# prod_plus_l-filters_v2.net
KiCad netlist of a schematic drawn in EAGLE
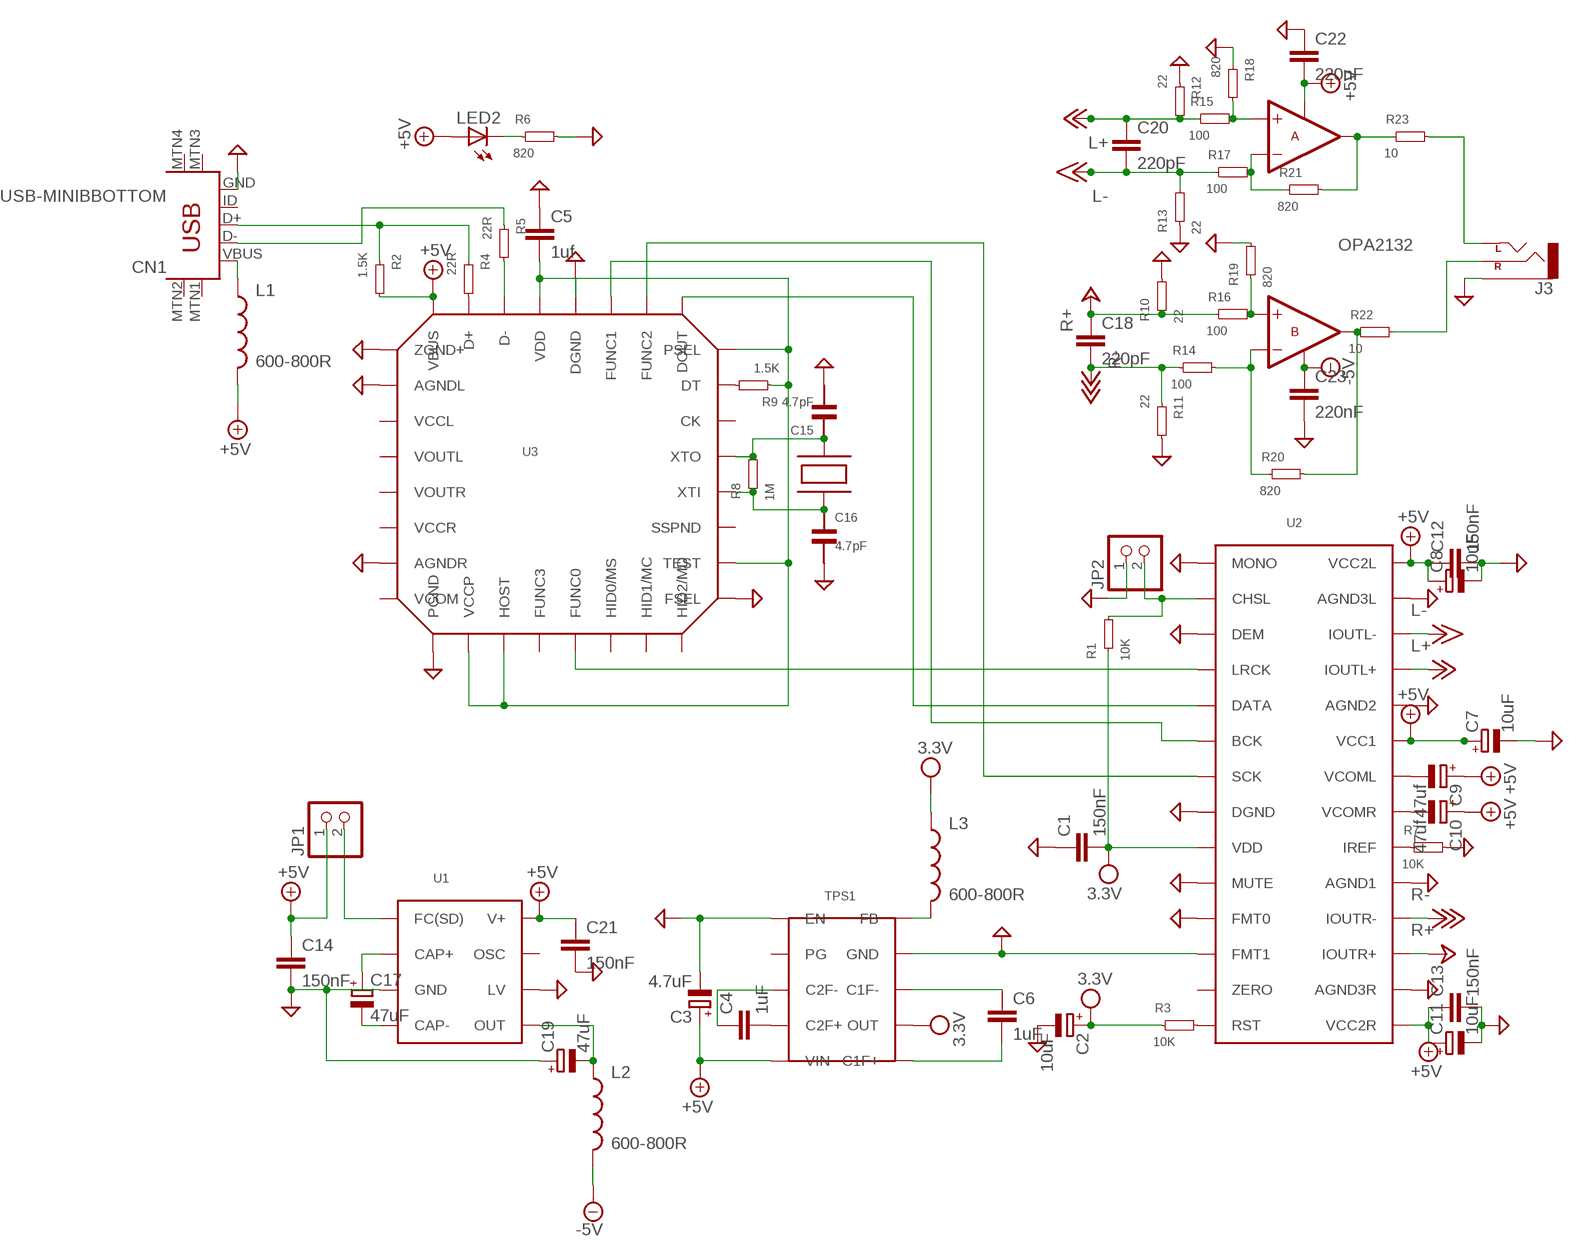
[diagram p0: schematic, sheet 1]

(export (version "E")
  (design (tool "Eeschema 10.0.6"))
  (components
    (comp (ref "C1")
      (value "150nF")
      (footprint "eagle-import:0805")
      (libsource (lib "eagle-import") (part "CAP0805"))
    )
    (comp (ref "C2")
      (value "10uF")
      (footprint "eagle-import:10UF_16V_PANA_M_CAP")
      (libsource (lib "eagle-import") (part "10UF/16V_PANA_M-CAP"))
    )
    (comp (ref "C3")
      (value "4.7uF")
      (footprint "eagle-import:10UF_16V_PANA_M_CAP")
      (libsource (lib "eagle-import") (part "4.7UF/50V_PANA_M-CAP"))
    )
    (comp (ref "C4")
      (value "1uF")
      (footprint "eagle-import:0805")
      (libsource (lib "eagle-import") (part "CAP0805"))
    )
    (comp (ref "C5")
      (value "1uf")
      (footprint "eagle-import:0805")
      (libsource (lib "eagle-import") (part "CAP0805"))
    )
    (comp (ref "C6")
      (value "1uF")
      (footprint "eagle-import:0805")
      (libsource (lib "eagle-import") (part "CAP0805"))
    )
    (comp (ref "C7")
      (value "10uF")
      (footprint "eagle-import:10UF_16V_PANA_M_CAP")
      (libsource (lib "eagle-import") (part "10UF/16V_PANA_M-CAP"))
    )
    (comp (ref "C8")
      (value "10uF")
      (footprint "eagle-import:10UF_16V_PANA_M_CAP")
      (libsource (lib "eagle-import") (part "10UF/16V_PANA_M-CAP"))
    )
    (comp (ref "C9")
      (value "47uf")
      (footprint "eagle-import:10UF_16V_PANA_M_CAP")
      (libsource (lib "eagle-import") (part "47UF/16V_PANA_M-CAP"))
    )
    (comp (ref "C10")
      (value "47uf")
      (footprint "eagle-import:10UF_16V_PANA_M_CAP")
      (libsource (lib "eagle-import") (part "47UF/16V_PANA_M-CAP"))
    )
    (comp (ref "C11")
      (value "10uF")
      (footprint "eagle-import:10UF_16V_PANA_M_CAP")
      (libsource (lib "eagle-import") (part "10UF/16V_PANA_M-CAP"))
    )
    (comp (ref "C12")
      (value "150nF")
      (footprint "eagle-import:0805")
      (libsource (lib "eagle-import") (part "CAP0805"))
    )
    (comp (ref "C13")
      (value "150nF")
      (footprint "eagle-import:0805")
      (libsource (lib "eagle-import") (part "CAP0805"))
    )
    (comp (ref "C14")
      (value "150nF")
      (footprint "eagle-import:0805")
      (libsource (lib "eagle-import") (part "CAP0805"))
    )
    (comp (ref "C15")
      (value "4.7pF")
      (footprint "eagle-import:4.7PF_CAP")
      (libsource (lib "eagle-import") (part "4.7PF_CAPMLCC"))
    )
    (comp (ref "C16")
      (value "4.7pF")
      (footprint "eagle-import:4.7PF_CAP")
      (libsource (lib "eagle-import") (part "4.7PF_CAPMLCC"))
    )
    (comp (ref "C17")
      (value "47uF")
      (footprint "eagle-import:10UF_16V_PANA_M_CAP")
      (libsource (lib "eagle-import") (part "47UF/16V_PANA_M-CAP"))
    )
    (comp (ref "C18")
      (value "220pF")
      (footprint "eagle-import:C050-045X075")
      (libsource (lib "eagle-import") (part "C-EU050-045X075"))
    )
    (comp (ref "C19")
      (value "47uF")
      (footprint "eagle-import:10UF_16V_PANA_M_CAP")
      (libsource (lib "eagle-import") (part "47UF/16V_PANA_M-CAP"))
    )
    (comp (ref "C20")
      (value "220pF")
      (footprint "eagle-import:C050-045X075")
      (libsource (lib "eagle-import") (part "C-EU050-045X075"))
    )
    (comp (ref "C21")
      (value "150nF")
      (footprint "eagle-import:0805")
      (libsource (lib "eagle-import") (part "CAP0805"))
    )
    (comp (ref "C22")
      (value "220nF")
      (footprint "eagle-import:0805")
      (libsource (lib "eagle-import") (part "22UF-6.3V-20%(0805)"))
    )
    (comp (ref "C23")
      (value "220nF")
      (footprint "eagle-import:0805")
      (libsource (lib "eagle-import") (part "22UF-6.3V-20%(0805)"))
    )
    (comp (ref "CN1")
      (value "USB-MINIBBOTTOM")
      (footprint "eagle-import:USB-MINIB")
      (libsource (lib "eagle-import") (part "USB-MINIBBOTTOM"))
    )
    (comp (ref "J3")
      (value "AUDIO-JACKPTH")
      (footprint "eagle-import:AUDIO-JACK")
      (libsource (lib "eagle-import") (part "AUDIO-JACKPTH"))
    )
    (comp (ref "JP1")
      (value "PINHD-1X2")
      (footprint "eagle-import:1X02")
      (libsource (lib "eagle-import") (part "PINHD-1X2"))
    )
    (comp (ref "JP2")
      (value "PINHD-1X2")
      (footprint "eagle-import:1X02")
      (libsource (lib "eagle-import") (part "PINHD-1X2"))
    )
    (comp (ref "L1")
      (value "600-800R")
      (footprint "eagle-import:0805")
      (libsource (lib "eagle-import") (part "INDUCTOR0805-IND"))
    )
    (comp (ref "L2")
      (value "600-800R")
      (footprint "eagle-import:0805")
      (libsource (lib "eagle-import") (part "INDUCTOR0805-IND"))
    )
    (comp (ref "L3")
      (value "600-800R")
      (footprint "eagle-import:0805")
      (libsource (lib "eagle-import") (part "INDUCTOR0805-IND"))
    )
    (comp (ref "LED2")
      (value "LED3MM")
      (footprint "eagle-import:LED3MM")
      (libsource (lib "eagle-import") (part "LED3MM"))
    )
    (comp (ref "OPA2132")
      (value "OPA2132DIP8")
      (footprint "eagle-import:DIP-8")
      (libsource (lib "eagle-import") (part "OPA2132DIP8"))
    )
    (comp (ref "R1")
      (value "10K")
      (footprint "eagle-import:1-8W_RES")
      (libsource (lib "eagle-import") (part "RESISTOR.125W"))
    )
    (comp (ref "R2")
      (value "1.5K")
      (footprint "eagle-import:1-8W_RES")
      (libsource (lib "eagle-import") (part "RESISTOR.125W"))
    )
    (comp (ref "R3")
      (value "10K")
      (footprint "eagle-import:1-8W_RES")
      (libsource (lib "eagle-import") (part "RESISTOR.125W"))
    )
    (comp (ref "R4")
      (value "22R")
      (footprint "eagle-import:1-8W_RES")
      (libsource (lib "eagle-import") (part "RESISTOR.125W"))
    )
    (comp (ref "R5")
      (value "22R")
      (footprint "eagle-import:1-8W_RES")
      (libsource (lib "eagle-import") (part "RESISTOR.125W"))
    )
    (comp (ref "R6")
      (value "820")
      (footprint "eagle-import:1-8W_RES")
      (libsource (lib "eagle-import") (part "RESISTOR.125W"))
    )
    (comp (ref "R7")
      (value "10K")
      (footprint "eagle-import:1-8W_RES")
      (libsource (lib "eagle-import") (part "RESISTOR.125W"))
    )
    (comp (ref "R8")
      (value "1M")
      (footprint "eagle-import:1-8W_RES")
      (libsource (lib "eagle-import") (part "RESISTOR.125W"))
    )
    (comp (ref "R9")
      (value "1.5K")
      (footprint "eagle-import:1-8W_RES")
      (libsource (lib "eagle-import") (part "RESISTOR.125W"))
    )
    (comp (ref "R10")
      (value "22")
      (footprint "eagle-import:1-8W_RES")
      (libsource (lib "eagle-import") (part "RESISTOR.125W"))
    )
    (comp (ref "R11")
      (value "22")
      (footprint "eagle-import:1-8W_RES")
      (libsource (lib "eagle-import") (part "RESISTOR.125W"))
    )
    (comp (ref "R12")
      (value "22")
      (footprint "eagle-import:1-8W_RES")
      (libsource (lib "eagle-import") (part "RESISTOR.125W"))
    )
    (comp (ref "R13")
      (value "22")
      (footprint "eagle-import:1-8W_RES")
      (libsource (lib "eagle-import") (part "RESISTOR.125W"))
    )
    (comp (ref "R14")
      (value "100")
      (footprint "eagle-import:1-8W_RES")
      (libsource (lib "eagle-import") (part "RESISTOR.125W"))
    )
    (comp (ref "R15")
      (value "100")
      (footprint "eagle-import:1-8W_RES")
      (libsource (lib "eagle-import") (part "RESISTOR.125W"))
    )
    (comp (ref "R16")
      (value "100")
      (footprint "eagle-import:1-8W_RES")
      (libsource (lib "eagle-import") (part "RESISTOR.125W"))
    )
    (comp (ref "R17")
      (value "100")
      (footprint "eagle-import:1-8W_RES")
      (libsource (lib "eagle-import") (part "RESISTOR.125W"))
    )
    (comp (ref "R18")
      (value "820")
      (footprint "eagle-import:1-8W_RES")
      (libsource (lib "eagle-import") (part "RESISTOR.125W"))
    )
    (comp (ref "R19")
      (value "820")
      (footprint "eagle-import:1-8W_RES")
      (libsource (lib "eagle-import") (part "RESISTOR.125W"))
    )
    (comp (ref "R20")
      (value "820")
      (footprint "eagle-import:1-8W_RES")
      (libsource (lib "eagle-import") (part "RESISTOR.125W"))
    )
    (comp (ref "R21")
      (value "820")
      (footprint "eagle-import:1-8W_RES")
      (libsource (lib "eagle-import") (part "RESISTOR.125W"))
    )
    (comp (ref "R22")
      (value "10")
      (footprint "eagle-import:1-8W_RES")
      (libsource (lib "eagle-import") (part "RESISTOR.125W"))
    )
    (comp (ref "R23")
      (value "10")
      (footprint "eagle-import:1-8W_RES")
      (libsource (lib "eagle-import") (part "RESISTOR.125W"))
    )
    (comp (ref "TPS1")
      (value "TPS60501DGS-10-BOTTOM")
      (footprint "eagle-import:DGS-10-BOTTOM_LYR")
      (libsource (lib "eagle-import") (part "TPS60501DGS-10-BOTTOM"))
    )
    (comp (ref "U1")
      (value "LM2662SO8-BOTTOM")
      (footprint "eagle-import:SOIC-8_BOTTOM-LYR")
      (libsource (lib "eagle-import") (part "LM2662SO8-BOTTOM"))
    )
    (comp (ref "U2")
      (value "PCM1794ADB_R-PDSO-G28-BOTTOM")
      (footprint "eagle-import:DB_R-PDSO-G28-BOTTOM_LYR")
      (libsource (lib "eagle-import") (part "PCM1794ADB_R-PDSO-G28-BOTTOM"))
    )
    (comp (ref "U3")
      (value "PCM2707QFP-32-BOTTOM")
      (footprint "eagle-import:PJT_(QFP-32)-BOTTOM_LYR")
      (libsource (lib "eagle-import") (part "PCM2707QFP-32-BOTTOM"))
    )
    (comp (ref "X1")
      (value "12MHZ")
      (footprint "eagle-import:CRYSTAL")
      (libsource (lib "eagle-import") (part "CRYSTAL"))
    )
  )
  (nets
    (net (code "1") (name "+5V") (class "Default")
      (node (ref "C10") (pin "+") (pinfunction "+_+") (pintype "passive"))
      (node (ref "C11") (pin "+") (pinfunction "+_+") (pintype "passive"))
      (node (ref "C12") (pin "1") (pinfunction "1_1") (pintype "passive"))
      (node (ref "C13") (pin "1") (pinfunction "1_1") (pintype "passive"))
      (node (ref "C14") (pin "1") (pinfunction "1_1") (pintype "passive"))
      (node (ref "C21") (pin "1") (pinfunction "1_1") (pintype "passive"))
      (node (ref "C22") (pin "2") (pinfunction "2_2") (pintype "passive"))
      (node (ref "C3") (pin "+") (pinfunction "+_+") (pintype "passive"))
      (node (ref "C7") (pin "+") (pinfunction "+_+") (pintype "passive"))
      (node (ref "C8") (pin "+") (pinfunction "+_+") (pintype "passive"))
      (node (ref "C9") (pin "+") (pinfunction "+_+") (pintype "passive"))
      (node (ref "JP1") (pin "1") (pinfunction "1_1") (pintype "passive"))
      (node (ref "L1") (pin "2") (pinfunction "2_2") (pintype "passive"))
      (node (ref "LED2") (pin "A") (pinfunction "A_A") (pintype "passive"))
      (node (ref "OPA2132") (pin "8") (pinfunction "8(+)_8") (pintype "bidirectional"))
      (node (ref "R2") (pin "P$2") (pinfunction "2_P$2") (pintype "bidirectional"))
      (node (ref "TPS1") (pin "5") (pinfunction "VIN_5") (pintype "bidirectional"))
      (node (ref "U1") (pin "8") (pinfunction "V+_8") (pintype "bidirectional"))
      (node (ref "U2") (pin "15") (pinfunction "VCC2R_15") (pintype "bidirectional"))
      (node (ref "U2") (pin "23") (pinfunction "VCC1_23") (pintype "bidirectional"))
      (node (ref "U2") (pin "28") (pinfunction "VCC2L_28") (pintype "bidirectional"))
      (node (ref "U3") (pin "24") (pinfunction "VBUS_24") (pintype "bidirectional"))
    )
    (net (code "2") (name "-5V") (class "Default")
      (node (ref "C23") (pin "1") (pinfunction "1_1") (pintype "passive"))
      (node (ref "L2") (pin "2") (pinfunction "2_2") (pintype "passive"))
      (node (ref "OPA2132") (pin "4") (pinfunction "4(-)_4") (pintype "bidirectional"))
    )
    (net (code "3") (name "3.3V") (class "Default")
      (node (ref "C1") (pin "2") (pinfunction "2_2") (pintype "passive"))
      (node (ref "C2") (pin "+") (pinfunction "+_+") (pintype "passive"))
      (node (ref "L3") (pin "1") (pinfunction "1_1") (pintype "passive"))
      (node (ref "R1") (pin "P$1") (pinfunction "1_P$1") (pintype "bidirectional"))
      (node (ref "R3") (pin "P$1") (pinfunction "1_P$1") (pintype "bidirectional"))
      (node (ref "TPS1") (pin "7") (pinfunction "OUT_7") (pintype "bidirectional"))
      (node (ref "U2") (pin "9") (pinfunction "VDD_9") (pintype "bidirectional"))
    )
    (net (code "4") (name "GND") (class "Default")
      (node (ref "C1") (pin "1") (pinfunction "1_1") (pintype "passive"))
      (node (ref "C11") (pin "-") (pinfunction "-_-") (pintype "passive"))
      (node (ref "C12") (pin "2") (pinfunction "2_2") (pintype "passive"))
      (node (ref "C13") (pin "2") (pinfunction "2_2") (pintype "passive"))
      (node (ref "C14") (pin "2") (pinfunction "2_2") (pintype "passive"))
      (node (ref "C15") (pin "2") (pinfunction "2_2") (pintype "bidirectional"))
      (node (ref "C16") (pin "2") (pinfunction "2_2") (pintype "bidirectional"))
      (node (ref "C19") (pin "+") (pinfunction "+_+") (pintype "passive"))
      (node (ref "C2") (pin "-") (pinfunction "-_-") (pintype "passive"))
      (node (ref "C21") (pin "2") (pinfunction "2_2") (pintype "passive"))
      (node (ref "C22") (pin "1") (pinfunction "1_1") (pintype "passive"))
      (node (ref "C23") (pin "2") (pinfunction "2_2") (pintype "passive"))
      (node (ref "C3") (pin "-") (pinfunction "-_-") (pintype "passive"))
      (node (ref "C5") (pin "1") (pinfunction "1_1") (pintype "passive"))
      (node (ref "C7") (pin "-") (pinfunction "-_-") (pintype "passive"))
      (node (ref "C8") (pin "-") (pinfunction "-_-") (pintype "passive"))
      (node (ref "CN1") (pin "GND") (pinfunction "GND_GND") (pintype "bidirectional"))
      (node (ref "J3") (pin "SLEEVE") (pinfunction "SLEEVE_SLEEVE") (pintype "bidirectional"))
      (node (ref "JP2") (pin "1") (pinfunction "1_1") (pintype "passive"))
      (node (ref "R10") (pin "P$2") (pinfunction "2_P$2") (pintype "bidirectional"))
      (node (ref "R11") (pin "P$2") (pinfunction "2_P$2") (pintype "bidirectional"))
      (node (ref "R12") (pin "P$1") (pinfunction "1_P$1") (pintype "bidirectional"))
      (node (ref "R13") (pin "P$1") (pinfunction "1_P$1") (pintype "bidirectional"))
      (node (ref "R18") (pin "P$1") (pinfunction "1_P$1") (pintype "bidirectional"))
      (node (ref "R19") (pin "P$2") (pinfunction "2_P$2") (pintype "bidirectional"))
      (node (ref "R6") (pin "P$2") (pinfunction "2_P$2") (pintype "bidirectional"))
      (node (ref "R7") (pin "P$2") (pinfunction "2_P$2") (pintype "bidirectional"))
      (node (ref "TPS1") (pin "1") (pinfunction "EN_1") (pintype "bidirectional"))
      (node (ref "TPS1") (pin "9") (pinfunction "GND_9") (pintype "bidirectional"))
      (node (ref "U1") (pin "3") (pinfunction "GND_3") (pintype "bidirectional"))
      (node (ref "U1") (pin "6") (pinfunction "LV_6") (pintype "bidirectional"))
      (node (ref "U2") (pin "1") (pinfunction "MONO_1") (pintype "bidirectional"))
      (node (ref "U2") (pin "10") (pinfunction "MUTE_10") (pintype "bidirectional"))
      (node (ref "U2") (pin "11") (pinfunction "FMT0_11") (pintype "bidirectional"))
      (node (ref "U2") (pin "12") (pinfunction "FMT1_12") (pintype "bidirectional"))
      (node (ref "U2") (pin "16") (pinfunction "AGND3R_16") (pintype "bidirectional"))
      (node (ref "U2") (pin "19") (pinfunction "AGND1_19") (pintype "bidirectional"))
      (node (ref "U2") (pin "24") (pinfunction "AGND2_24") (pintype "bidirectional"))
      (node (ref "U2") (pin "27") (pinfunction "AGND3L_27") (pintype "bidirectional"))
      (node (ref "U2") (pin "3") (pinfunction "DEM_3") (pintype "bidirectional"))
      (node (ref "U2") (pin "8") (pinfunction "DGND_8") (pintype "bidirectional"))
      (node (ref "U3") (pin "1") (pinfunction "PGND_1") (pintype "bidirectional"))
      (node (ref "U3") (pin "20") (pinfunction "DGND_20") (pintype "bidirectional"))
      (node (ref "U3") (pin "25") (pinfunction "ZGND+_25") (pintype "bidirectional"))
      (node (ref "U3") (pin "26") (pinfunction "AGNDL_26") (pintype "bidirectional"))
      (node (ref "U3") (pin "31") (pinfunction "AGNDR_31") (pintype "bidirectional"))
      (node (ref "U3") (pin "9") (pinfunction "FSEL_9") (pintype "bidirectional"))
    )
    (net (code "5") (name "L+") (class "Default")
      (node (ref "C20") (pin "1") (pinfunction "1_1") (pintype "passive"))
      (node (ref "R12") (pin "P$2") (pinfunction "2_P$2") (pintype "bidirectional"))
      (node (ref "R15") (pin "P$1") (pinfunction "1_P$1") (pintype "bidirectional"))
      (node (ref "U2") (pin "25") (pinfunction "IOUTL+_25") (pintype "bidirectional"))
    )
    (net (code "6") (name "L-") (class "Default")
      (node (ref "C20") (pin "2") (pinfunction "2_2") (pintype "passive"))
      (node (ref "R13") (pin "P$2") (pinfunction "2_P$2") (pintype "bidirectional"))
      (node (ref "R17") (pin "P$1") (pinfunction "1_P$1") (pintype "bidirectional"))
      (node (ref "U2") (pin "26") (pinfunction "IOUTL-_26") (pintype "bidirectional"))
    )
    (net (code "7") (name "Net-(CN1-PadVBUS)") (class "Default")
      (node (ref "CN1") (pin "VBUS") (pinfunction "VBUS_VBUS") (pintype "bidirectional"))
      (node (ref "L1") (pin "1") (pinfunction "1_1") (pintype "passive"))
    )
    (net (code "8") (name "Net-(J3-LEFT)") (class "Default")
      (node (ref "J3") (pin "TIP") (pinfunction "LEFT_TIP") (pintype "bidirectional"))
      (node (ref "R23") (pin "P$2") (pinfunction "2_P$2") (pintype "bidirectional"))
    )
    (net (code "9") (name "Net-(J3-RIGHT)") (class "Default")
      (node (ref "J3") (pin "RING") (pinfunction "RIGHT_RING") (pintype "bidirectional"))
      (node (ref "R22") (pin "P$2") (pinfunction "2_P$2") (pintype "bidirectional"))
    )
    (net (code "10") (name "Net-(LED2-C)") (class "Default")
      (node (ref "LED2") (pin "K") (pinfunction "C_K") (pintype "passive"))
      (node (ref "R6") (pin "P$1") (pinfunction "1_P$1") (pintype "bidirectional"))
    )
    (net (code "11") (name "Net-(R1-2)") (class "Default")
      (node (ref "JP2") (pin "2") (pinfunction "2_2") (pintype "passive"))
      (node (ref "R1") (pin "P$2") (pinfunction "2_P$2") (pintype "bidirectional"))
      (node (ref "U2") (pin "2") (pinfunction "CHSL_2") (pintype "bidirectional"))
    )
    (net (code "12") (name "Net-(R2-1)") (class "Default")
      (node (ref "CN1") (pin "D+") (pinfunction "D+_D+") (pintype "bidirectional"))
      (node (ref "R2") (pin "P$1") (pinfunction "1_P$1") (pintype "bidirectional"))
      (node (ref "R4") (pin "P$1") (pinfunction "1_P$1") (pintype "bidirectional"))
    )
    (net (code "13") (name "Net-(R3-2)") (class "Default")
      (node (ref "R3") (pin "P$2") (pinfunction "2_P$2") (pintype "bidirectional"))
      (node (ref "U2") (pin "14") (pinfunction "RST_14") (pintype "bidirectional"))
    )
    (net (code "14") (name "Net-(R4-2)") (class "Default")
      (node (ref "R4") (pin "P$2") (pinfunction "2_P$2") (pintype "bidirectional"))
      (node (ref "U3") (pin "23") (pinfunction "D+_23") (pintype "bidirectional"))
    )
    (net (code "15") (name "Net-(R5-1)") (class "Default")
      (node (ref "CN1") (pin "D-") (pinfunction "D-_D-") (pintype "bidirectional"))
      (node (ref "R5") (pin "P$1") (pinfunction "1_P$1") (pintype "bidirectional"))
    )
    (net (code "16") (name "Net-(R5-2)") (class "Default")
      (node (ref "R5") (pin "P$2") (pinfunction "2_P$2") (pintype "bidirectional"))
      (node (ref "U3") (pin "22") (pinfunction "D-_22") (pintype "bidirectional"))
    )
    (net (code "17") (name "Net-(R7-1)") (class "Default")
      (node (ref "R7") (pin "P$1") (pinfunction "1_P$1") (pintype "bidirectional"))
      (node (ref "U2") (pin "20") (pinfunction "IREF_20") (pintype "bidirectional"))
    )
    (net (code "18") (name "Net-(R8-1)") (class "Default")
      (node (ref "C16") (pin "1") (pinfunction "1_1") (pintype "bidirectional"))
      (node (ref "R8") (pin "P$1") (pinfunction "1_P$1") (pintype "bidirectional"))
      (node (ref "U3") (pin "12") (pinfunction "XTI_12") (pintype "bidirectional"))
      (node (ref "X1") (pin "1") (pinfunction "1_1") (pintype "bidirectional"))
    )
    (net (code "19") (name "Net-(R8-2)") (class "Default")
      (node (ref "C15") (pin "1") (pinfunction "1_1") (pintype "bidirectional"))
      (node (ref "R8") (pin "P$2") (pinfunction "2_P$2") (pintype "bidirectional"))
      (node (ref "U3") (pin "13") (pinfunction "XTO_13") (pintype "bidirectional"))
      (node (ref "X1") (pin "2") (pinfunction "2_2") (pintype "bidirectional"))
    )
    (net (code "20") (name "Net-(R9-1)") (class "Default")
      (node (ref "C5") (pin "2") (pinfunction "2_2") (pintype "passive"))
      (node (ref "R9") (pin "P$1") (pinfunction "1_P$1") (pintype "bidirectional"))
      (node (ref "U3") (pin "10") (pinfunction "TEST_10") (pintype "bidirectional"))
      (node (ref "U3") (pin "16") (pinfunction "PSEL_16") (pintype "bidirectional"))
      (node (ref "U3") (pin "2") (pinfunction "VCCP_2") (pintype "bidirectional"))
      (node (ref "U3") (pin "21") (pinfunction "VDD_21") (pintype "bidirectional"))
      (node (ref "U3") (pin "3") (pinfunction "HOST_3") (pintype "bidirectional"))
    )
    (net (code "21") (name "Net-(R9-2)") (class "Default")
      (node (ref "R9") (pin "P$2") (pinfunction "2_P$2") (pintype "bidirectional"))
      (node (ref "U3") (pin "15") (pinfunction "DT_15") (pintype "bidirectional"))
    )
    (net (code "22") (name "Net-(R14-2)") (class "Default")
      (node (ref "OPA2132") (pin "6") (pinfunction "6_6") (pintype "input"))
      (node (ref "R14") (pin "P$2") (pinfunction "2_P$2") (pintype "bidirectional"))
      (node (ref "R20") (pin "P$1") (pinfunction "1_P$1") (pintype "bidirectional"))
    )
    (net (code "23") (name "Net-(R15-2)") (class "Default")
      (node (ref "OPA2132") (pin "3") (pinfunction "3_3") (pintype "input"))
      (node (ref "R15") (pin "P$2") (pinfunction "2_P$2") (pintype "bidirectional"))
      (node (ref "R18") (pin "P$2") (pinfunction "2_P$2") (pintype "bidirectional"))
    )
    (net (code "24") (name "Net-(R16-2)") (class "Default")
      (node (ref "OPA2132") (pin "5") (pinfunction "5_5") (pintype "input"))
      (node (ref "R16") (pin "P$2") (pinfunction "2_P$2") (pintype "bidirectional"))
      (node (ref "R19") (pin "P$1") (pinfunction "1_P$1") (pintype "bidirectional"))
    )
    (net (code "25") (name "Net-(R17-2)") (class "Default")
      (node (ref "OPA2132") (pin "2") (pinfunction "2_2") (pintype "input"))
      (node (ref "R17") (pin "P$2") (pinfunction "2_P$2") (pintype "bidirectional"))
      (node (ref "R21") (pin "P$1") (pinfunction "1_P$1") (pintype "bidirectional"))
    )
    (net (code "26") (name "Net-(R20-2)") (class "Default")
      (node (ref "OPA2132") (pin "7") (pinfunction "7_7") (pintype "output"))
      (node (ref "R20") (pin "P$2") (pinfunction "2_P$2") (pintype "bidirectional"))
      (node (ref "R22") (pin "P$1") (pinfunction "1_P$1") (pintype "bidirectional"))
    )
    (net (code "27") (name "Net-(R21-2)") (class "Default")
      (node (ref "OPA2132") (pin "1") (pinfunction "1_1") (pintype "output"))
      (node (ref "R21") (pin "P$2") (pinfunction "2_P$2") (pintype "bidirectional"))
      (node (ref "R23") (pin "P$1") (pinfunction "1_P$1") (pintype "bidirectional"))
    )
    (net (code "28") (name "Net-(TPS1-C1F+)") (class "Default")
      (node (ref "C6") (pin "2") (pinfunction "2_2") (pintype "passive"))
      (node (ref "TPS1") (pin "6") (pinfunction "C1F+_6") (pintype "bidirectional"))
    )
    (net (code "29") (name "Net-(TPS1-C1F-)") (class "Default")
      (node (ref "C6") (pin "1") (pinfunction "1_1") (pintype "passive"))
      (node (ref "TPS1") (pin "8") (pinfunction "C1F-_8") (pintype "bidirectional"))
    )
    (net (code "30") (name "Net-(TPS1-C2F+)") (class "Default")
      (node (ref "C4") (pin "2") (pinfunction "2_2") (pintype "passive"))
      (node (ref "TPS1") (pin "4") (pinfunction "C2F+_4") (pintype "bidirectional"))
    )
    (net (code "31") (name "Net-(TPS1-C2F-)") (class "Default")
      (node (ref "C4") (pin "1") (pinfunction "1_1") (pintype "passive"))
      (node (ref "TPS1") (pin "3") (pinfunction "C2F-_3") (pintype "bidirectional"))
    )
    (net (code "32") (name "Net-(TPS1-FB)") (class "Default")
      (node (ref "L3") (pin "2") (pinfunction "2_2") (pintype "passive"))
      (node (ref "TPS1") (pin "10") (pinfunction "FB_10") (pintype "bidirectional"))
    )
    (net (code "33") (name "Net-(U1-CAP+)") (class "Default")
      (node (ref "C17") (pin "+") (pinfunction "+_+") (pintype "passive"))
      (node (ref "U1") (pin "2") (pinfunction "CAP+_2") (pintype "bidirectional"))
    )
    (net (code "34") (name "Net-(U1-CAP-)") (class "Default")
      (node (ref "C17") (pin "-") (pinfunction "-_-") (pintype "passive"))
      (node (ref "U1") (pin "4") (pinfunction "CAP-_4") (pintype "bidirectional"))
    )
    (net (code "35") (name "Net-(U1-FC(SD))") (class "Default")
      (node (ref "JP1") (pin "2") (pinfunction "2_2") (pintype "passive"))
      (node (ref "U1") (pin "1") (pinfunction "FC(SD)_1") (pintype "bidirectional"))
    )
    (net (code "36") (name "Net-(U1-OUT)") (class "Default")
      (node (ref "C19") (pin "-") (pinfunction "-_-") (pintype "passive"))
      (node (ref "L2") (pin "1") (pinfunction "1_1") (pintype "passive"))
      (node (ref "U1") (pin "5") (pinfunction "OUT_5") (pintype "bidirectional"))
    )
    (net (code "37") (name "Net-(U2-BCK)") (class "Default")
      (node (ref "U2") (pin "6") (pinfunction "BCK_6") (pintype "bidirectional"))
      (node (ref "U3") (pin "19") (pinfunction "FUNC1_19") (pintype "bidirectional"))
    )
    (net (code "38") (name "Net-(U2-DATA)") (class "Default")
      (node (ref "U2") (pin "5") (pinfunction "DATA_5") (pintype "bidirectional"))
      (node (ref "U3") (pin "17") (pinfunction "DOUT_17") (pintype "bidirectional"))
    )
    (net (code "39") (name "Net-(U2-LRCK)") (class "Default")
      (node (ref "U2") (pin "4") (pinfunction "LRCK_4") (pintype "bidirectional"))
      (node (ref "U3") (pin "5") (pinfunction "FUNC0_5") (pintype "bidirectional"))
    )
    (net (code "40") (name "Net-(U2-SCK)") (class "Default")
      (node (ref "U2") (pin "7") (pinfunction "SCK_7") (pintype "bidirectional"))
      (node (ref "U3") (pin "18") (pinfunction "FUNC2_18") (pintype "bidirectional"))
    )
    (net (code "41") (name "Net-(U2-VCOML)") (class "Default")
      (node (ref "C9") (pin "-") (pinfunction "-_-") (pintype "passive"))
      (node (ref "U2") (pin "22") (pinfunction "VCOML_22") (pintype "bidirectional"))
    )
    (net (code "42") (name "Net-(U2-VCOMR)") (class "Default")
      (node (ref "C10") (pin "-") (pinfunction "-_-") (pintype "passive"))
      (node (ref "U2") (pin "21") (pinfunction "VCOMR_21") (pintype "bidirectional"))
    )
    (net (code "43") (name "R+") (class "Default")
      (node (ref "C18") (pin "1") (pinfunction "1_1") (pintype "passive"))
      (node (ref "R10") (pin "P$1") (pinfunction "1_P$1") (pintype "bidirectional"))
      (node (ref "R16") (pin "P$1") (pinfunction "1_P$1") (pintype "bidirectional"))
      (node (ref "U2") (pin "17") (pinfunction "IOUTR+_17") (pintype "bidirectional"))
    )
    (net (code "44") (name "R-") (class "Default")
      (node (ref "C18") (pin "2") (pinfunction "2_2") (pintype "passive"))
      (node (ref "R11") (pin "P$1") (pinfunction "1_P$1") (pintype "bidirectional"))
      (node (ref "R14") (pin "P$1") (pinfunction "1_P$1") (pintype "bidirectional"))
      (node (ref "U2") (pin "18") (pinfunction "IOUTR-_18") (pintype "bidirectional"))
    )
    (net (code "45") (name "unconnected-(CN1-PadID)") (class "Default")
      (node (ref "CN1") (pin "ID") (pinfunction "ID_ID") (pintype "bidirectional"))
    )
    (net (code "46") (name "unconnected-(CN1-PadMTN1)") (class "Default")
      (node (ref "CN1") (pin "MTN1") (pinfunction "MTN1_MTN1") (pintype "bidirectional"))
    )
    (net (code "47") (name "unconnected-(CN1-PadMTN2)") (class "Default")
      (node (ref "CN1") (pin "MTN2") (pinfunction "MTN2_MTN2") (pintype "bidirectional"))
    )
    (net (code "48") (name "unconnected-(CN1-PadMTN3)") (class "Default")
      (node (ref "CN1") (pin "MTN3") (pinfunction "MTN3_MTN3") (pintype "bidirectional"))
    )
    (net (code "49") (name "unconnected-(CN1-PadMTN4)") (class "Default")
      (node (ref "CN1") (pin "MTN4") (pinfunction "MTN4_MTN4") (pintype "bidirectional"))
    )
    (net (code "50") (name "unconnected-(TPS1-PG-Pad2)") (class "Default")
      (node (ref "TPS1") (pin "2") (pinfunction "PG_2") (pintype "bidirectional"))
    )
    (net (code "51") (name "unconnected-(U1-OSC-Pad7)") (class "Default")
      (node (ref "U1") (pin "7") (pinfunction "OSC_7") (pintype "bidirectional"))
    )
    (net (code "52") (name "unconnected-(U2-ZERO-Pad13)") (class "Default")
      (node (ref "U2") (pin "13") (pinfunction "ZERO_13") (pintype "bidirectional"))
    )
    (net (code "53") (name "unconnected-(U3-CK-Pad14)") (class "Default")
      (node (ref "U3") (pin "14") (pinfunction "CK_14") (pintype "bidirectional"))
    )
    (net (code "54") (name "unconnected-(U3-FUNC3-Pad4)") (class "Default")
      (node (ref "U3") (pin "4") (pinfunction "FUNC3_4") (pintype "bidirectional"))
    )
    (net (code "55") (name "unconnected-(U3-HID0{slash}MS-Pad6)") (class "Default")
      (node (ref "U3") (pin "6") (pinfunction "HID0/MS_6") (pintype "bidirectional"))
    )
    (net (code "56") (name "unconnected-(U3-HID1{slash}MC-Pad7)") (class "Default")
      (node (ref "U3") (pin "7") (pinfunction "HID1/MC_7") (pintype "bidirectional"))
    )
    (net (code "57") (name "unconnected-(U3-HID2{slash}MD-Pad8)") (class "Default")
      (node (ref "U3") (pin "8") (pinfunction "HID2/MD_8") (pintype "bidirectional"))
    )
    (net (code "58") (name "unconnected-(U3-SSPND-Pad11)") (class "Default")
      (node (ref "U3") (pin "11") (pinfunction "SSPND_11") (pintype "bidirectional"))
    )
    (net (code "59") (name "unconnected-(U3-VCCL-Pad27)") (class "Default")
      (node (ref "U3") (pin "27") (pinfunction "VCCL_27") (pintype "bidirectional"))
    )
    (net (code "60") (name "unconnected-(U3-VCCR-Pad30)") (class "Default")
      (node (ref "U3") (pin "30") (pinfunction "VCCR_30") (pintype "bidirectional"))
    )
    (net (code "61") (name "unconnected-(U3-VCOM-Pad32)") (class "Default")
      (node (ref "U3") (pin "32") (pinfunction "VCOM_32") (pintype "bidirectional"))
    )
    (net (code "62") (name "unconnected-(U3-VOUTL-Pad28)") (class "Default")
      (node (ref "U3") (pin "28") (pinfunction "VOUTL_28") (pintype "bidirectional"))
    )
    (net (code "63") (name "unconnected-(U3-VOUTR-Pad29)") (class "Default")
      (node (ref "U3") (pin "29") (pinfunction "VOUTR_29") (pintype "bidirectional"))
    )
  )
)
